# 05_-POWER.net
KiCad netlist of a schematic drawn in Altium Designer
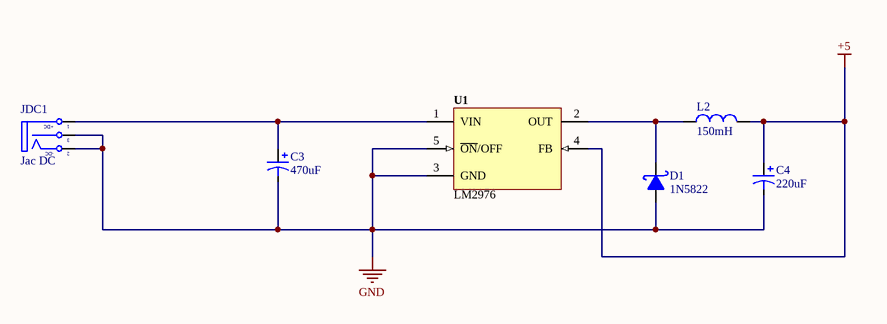
[diagram p0: [05]-POWER.SchDoc]

(export (version "E")
  (design (tool "Eeschema 10.0.6"))
  (components
    (comp (ref "C3")
      (value "470uF")
      (footprint "C5mm")
      (description "Polarized Capacitor (Axial)")
      (fields (field (name "PUBLISHER") "Altium Limited"))
      (libsource (lib "My Library") (part "Cap Pol"))
    )
    (comp (ref "C4")
      (value "220uF")
      (footprint "C5mm")
      (description "Polarized Capacitor (Axial)")
      (fields (field (name "PUBLISHER") "Altium Limited"))
      (libsource (lib "My Library") (part "Cap Pol"))
    )
    (comp (ref "D1")
      (value "1N5822")
      (footprint "SMA")
      (description "Schottky Rectifiers")
      (libsource (lib "My Library") (part "1N5822"))
    )
    (comp (ref "JDC1")
      (value "Jac DC")
      (footprint "DC-IN")
      (description "Jac DC input")
      (libsource (lib "My Library") (part "DCIN"))
    )
    (comp (ref "L2")
      (value "150mH")
      (footprint "L-SMD-M-7.3x4.5")
      (description "Inductor")
      (libsource (lib "My Library") (part "Inductor"))
    )
    (comp (ref "U1") (value "LM2976") (footprint "TO-263") (libsource (lib "My Library") (part "LM2596")))
  )
  (nets
    (net (code "1") (name "+5") (class "Default")
      (node (ref "C4") (pin "1") (pinfunction "1_1") (pintype "passive"))
      (node (ref "L2") (pin "2") (pinfunction "2_2") (pintype "passive"))
      (node (ref "U1") (pin "4") (pinfunction "FB_4") (pintype "input"))
    )
    (net (code "2") (name "GND") (class "Default")
      (node (ref "C3") (pin "2") (pinfunction "2_2") (pintype "passive"))
      (node (ref "C4") (pin "2") (pinfunction "2_2") (pintype "passive"))
      (node (ref "D1") (pin "1") (pinfunction "A_1") (pintype "passive"))
      (node (ref "JDC1") (pin "2") (pinfunction "TN_2") (pintype "passive"))
      (node (ref "JDC1") (pin "3") (pinfunction "S_3") (pintype "power_in"))
      (node (ref "U1") (pin "3") (pinfunction "GND_3") (pintype "power_in"))
      (node (ref "U1") (pin "5") (pinfunction "~{ON}/OFF_5") (pintype "input"))
    )
    (net (code "3") (name "Net-(D1-K)") (class "Default")
      (node (ref "D1") (pin "2") (pinfunction "K_2") (pintype "passive"))
      (node (ref "L2") (pin "1") (pinfunction "1_1") (pintype "passive"))
      (node (ref "U1") (pin "2") (pinfunction "OUT_2") (pintype "power_in"))
    )
    (net (code "4") (name "Net-(JDC1-T)") (class "Default")
      (node (ref "C3") (pin "1") (pinfunction "1_1") (pintype "passive"))
      (node (ref "JDC1") (pin "1") (pinfunction "T_1") (pintype "passive"))
      (node (ref "U1") (pin "1") (pinfunction "VIN_1") (pintype "power_in"))
    )
  )
)
